# LedControl.net
KiCad netlist of a schematic drawn in Altium Designer
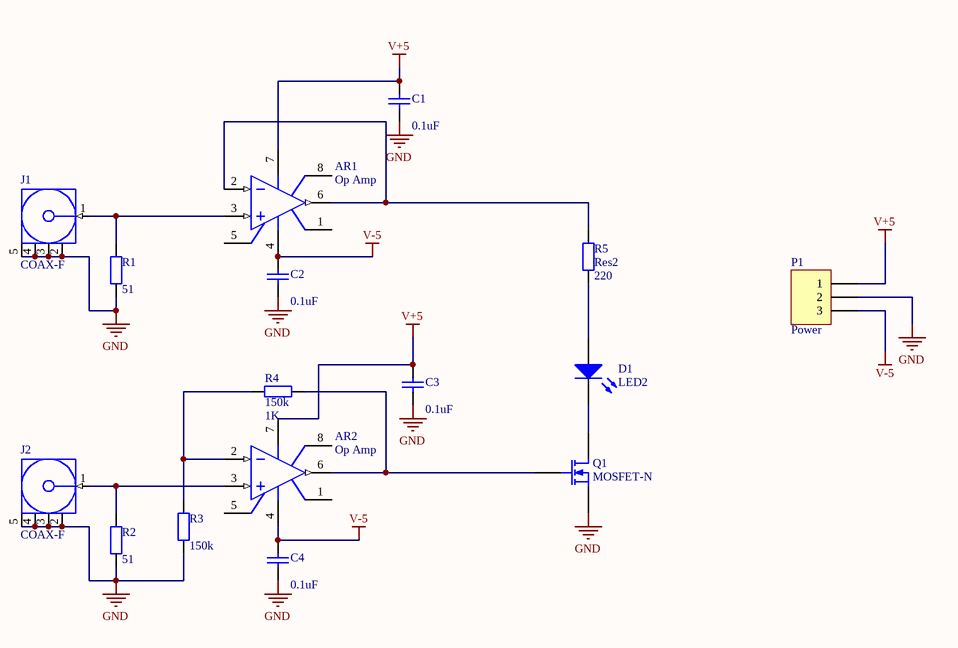
[diagram p0: LedControl.SchDoc]

(export (version "E")
  (design (tool "Eeschema 10.0.6"))
  (components
    (comp (ref "AR1")
      (value "Op Amp")
      (footprint "H-08A")
      (description "FET Operational Amplifier")
      (fields (field (name "PUBLISHER") "Altium Limited"))
      (libsource (lib "Miscellaneous Devices") (part "Op Amp"))
    )
    (comp (ref "AR2")
      (value "Op Amp")
      (footprint "H-08A")
      (description "FET Operational Amplifier")
      (fields (field (name "PUBLISHER") "Altium Limited"))
      (libsource (lib "Miscellaneous Devices") (part "Op Amp"))
    )
    (comp (ref "C1")
      (value "0.1uF")
      (footprint "RAD-0.3")
      (description "Capacitor")
      (fields (field (name "PUBLISHER") "Altium Limited"))
      (libsource (lib "Miscellaneous Devices") (part "Cap"))
    )
    (comp (ref "C2")
      (value "0.1uF")
      (footprint "RAD-0.3")
      (description "Capacitor")
      (fields (field (name "PUBLISHER") "Altium Limited"))
      (libsource (lib "Miscellaneous Devices") (part "Cap"))
    )
    (comp (ref "C3")
      (value "0.1uF")
      (footprint "RAD-0.3")
      (description "Capacitor")
      (fields (field (name "PUBLISHER") "Altium Limited"))
      (libsource (lib "Miscellaneous Devices") (part "Cap"))
    )
    (comp (ref "C4")
      (value "0.1uF")
      (footprint "RAD-0.3")
      (description "Capacitor")
      (fields (field (name "PUBLISHER") "Altium Limited"))
      (libsource (lib "Miscellaneous Devices") (part "Cap"))
    )
    (comp (ref "D1")
      (value "LED2")
      (footprint "3.2X1.6X1.1")
      (description "Typical RED, GREEN, YELLOW, AMBER GaAs LED")
      (fields (field (name "PUBLISHER") "Altium Limited"))
      (libsource (lib "Miscellaneous Devices") (part "LED2"))
    )
    (comp (ref "J1")
      (value "COAX-F")
      (footprint "MCX5.08-H5")
      (fields (field (name "PUBLISHER") "Altium Limited"))
      (libsource (lib "Miscellaneous Connectors") (part "COAX-F"))
    )
    (comp (ref "J2")
      (value "COAX-F")
      (footprint "MCX5.08-H5")
      (fields (field (name "PUBLISHER") "Altium Limited"))
      (libsource (lib "Miscellaneous Connectors") (part "COAX-F"))
    )
    (comp (ref "P1")
      (value "Power")
      (footprint "HDR1X3")
      (description "Header, 3-Pin")
      (fields (field (name "PUBLISHER") "Altium Limited"))
      (libsource (lib "Miscellaneous Connectors") (part "Header 3"))
    )
    (comp (ref "Q1")
      (value "MOSFET-N")
      (footprint "E3")
      (description "N-Channel MOSFET")
      (fields (field (name "PUBLISHER") "Altium Limited"))
      (libsource (lib "Miscellaneous Devices") (part "MOSFET-N"))
    )
    (comp (ref "R1")
      (value "51")
      (footprint "AXIAL-0.4")
      (description "Resistor")
      (fields (field (name "PUBLISHER") "Altium Limited"))
      (libsource (lib "Miscellaneous Devices") (part "Res2"))
    )
    (comp (ref "R2")
      (value "51")
      (footprint "AXIAL-0.4")
      (description "Resistor")
      (fields (field (name "PUBLISHER") "Altium Limited"))
      (libsource (lib "Miscellaneous Devices") (part "Res2"))
    )
    (comp (ref "R3")
      (value "150k")
      (footprint "AXIAL-0.4")
      (description "Resistor")
      (fields (field (name "PUBLISHER") "Altium Limited"))
      (libsource (lib "Miscellaneous Devices") (part "Res2"))
    )
    (comp (ref "R4")
      (value "150k")
      (footprint "AXIAL-0.4")
      (description "Resistor")
      (fields (field (name "ALTIUM_VALUE") "1K") (field (name "PUBLISHER") "Altium Limited"))
      (libsource (lib "") (part "Res2_1"))
    )
    (comp (ref "R5")
      (value "Res2")
      (footprint "AXIAL-0.4")
      (description "Resistor")
      (fields (field (name "ALTIUM_VALUE") "220") (field (name "PUBLISHER") "Altium Limited"))
      (libsource (lib "Miscellaneous Devices") (part "Res2"))
    )
  )
  (nets
    (net (code "1") (name "GND") (class "Default")
      (node (ref "C1") (pin "1") (pinfunction "1_1") (pintype "passive"))
      (node (ref "C2") (pin "1") (pinfunction "1_1") (pintype "passive"))
      (node (ref "C3") (pin "1") (pinfunction "1_1") (pintype "passive"))
      (node (ref "C4") (pin "1") (pinfunction "1_1") (pintype "passive"))
      (node (ref "J1") (pin "2") (pinfunction "GND_2") (pintype "power_in"))
      (node (ref "J1") (pin "3") (pinfunction "GND_3") (pintype "power_in"))
      (node (ref "J1") (pin "4") (pinfunction "GND_4") (pintype "power_in"))
      (node (ref "J1") (pin "5") (pinfunction "GND_5") (pintype "power_in"))
      (node (ref "J2") (pin "2") (pinfunction "GND_2") (pintype "power_in"))
      (node (ref "J2") (pin "3") (pinfunction "GND_3") (pintype "power_in"))
      (node (ref "J2") (pin "4") (pinfunction "GND_4") (pintype "power_in"))
      (node (ref "J2") (pin "5") (pinfunction "GND_5") (pintype "power_in"))
      (node (ref "P1") (pin "2") (pinfunction "2_2") (pintype "passive"))
      (node (ref "Q1") (pin "3") (pinfunction "S_3") (pintype "passive"))
      (node (ref "R1") (pin "1") (pinfunction "1_1") (pintype "passive"))
      (node (ref "R2") (pin "1") (pinfunction "1_1") (pintype "passive"))
      (node (ref "R3") (pin "1") (pinfunction "1_1") (pintype "passive"))
    )
    (net (code "2") (name "Net-(AR1-IN+)") (class "Default")
      (node (ref "AR1") (pin "3") (pinfunction "IN+_3") (pintype "input"))
      (node (ref "J1") (pin "1") (pinfunction "Signal_1") (pintype "input"))
      (node (ref "R1") (pin "2") (pinfunction "2_2") (pintype "passive"))
    )
    (net (code "3") (name "Net-(AR1-IN-)") (class "Default")
      (node (ref "AR1") (pin "2") (pinfunction "IN-_2") (pintype "input"))
      (node (ref "AR1") (pin "6") (pinfunction "OUT_6") (pintype "output"))
      (node (ref "R5") (pin "2") (pinfunction "2_2") (pintype "passive"))
    )
    (net (code "4") (name "Net-(AR2-IN+)") (class "Default")
      (node (ref "AR2") (pin "3") (pinfunction "IN+_3") (pintype "input"))
      (node (ref "J2") (pin "1") (pinfunction "Signal_1") (pintype "input"))
      (node (ref "R2") (pin "2") (pinfunction "2_2") (pintype "passive"))
    )
    (net (code "5") (name "Net-(AR2-IN-)") (class "Default")
      (node (ref "AR2") (pin "2") (pinfunction "IN-_2") (pintype "input"))
      (node (ref "R3") (pin "2") (pinfunction "2_2") (pintype "passive"))
      (node (ref "R4") (pin "1") (pinfunction "1_1") (pintype "passive"))
    )
    (net (code "6") (name "Net-(AR2-OUT)") (class "Default")
      (node (ref "AR2") (pin "6") (pinfunction "OUT_6") (pintype "output"))
      (node (ref "Q1") (pin "2") (pinfunction "G_2") (pintype "passive"))
      (node (ref "R4") (pin "2") (pinfunction "2_2") (pintype "passive"))
    )
    (net (code "7") (name "Net-(D1-A)") (class "Default")
      (node (ref "D1") (pin "1") (pinfunction "A_1") (pintype "passive"))
      (node (ref "R5") (pin "1") (pinfunction "1_1") (pintype "passive"))
    )
    (net (code "8") (name "Net-(D1-K)") (class "Default")
      (node (ref "D1") (pin "2") (pinfunction "K_2") (pintype "passive"))
      (node (ref "Q1") (pin "1") (pinfunction "D_1") (pintype "passive"))
    )
    (net (code "9") (name "V+5") (class "Default")
      (node (ref "AR1") (pin "7") (pinfunction "V+_7") (pintype "power_in"))
      (node (ref "AR2") (pin "7") (pinfunction "V+_7") (pintype "power_in"))
      (node (ref "C1") (pin "2") (pinfunction "2_2") (pintype "passive"))
      (node (ref "C3") (pin "2") (pinfunction "2_2") (pintype "passive"))
      (node (ref "P1") (pin "1") (pinfunction "1_1") (pintype "passive"))
    )
    (net (code "10") (name "V-5") (class "Default")
      (node (ref "AR1") (pin "4") (pinfunction "V-_4") (pintype "power_in"))
      (node (ref "AR2") (pin "4") (pinfunction "V-_4") (pintype "power_in"))
      (node (ref "C2") (pin "2") (pinfunction "2_2") (pintype "passive"))
      (node (ref "C4") (pin "2") (pinfunction "2_2") (pintype "passive"))
      (node (ref "P1") (pin "3") (pinfunction "3_3") (pintype "passive"))
    )
    (net (code "11") (name "unconnected-(AR1-OS_NUL-Pad1)") (class "Default")
      (node (ref "AR1") (pin "1") (pinfunction "OS_NUL_1") (pintype "passive"))
    )
    (net (code "12") (name "unconnected-(AR1-OS_NUL-Pad5)") (class "Default")
      (node (ref "AR1") (pin "5") (pinfunction "OS_NUL_5") (pintype "passive"))
    )
    (net (code "13") (name "unconnected-(AR1-TAB-Pad8)") (class "Default")
      (node (ref "AR1") (pin "8") (pinfunction "TAB_8") (pintype "passive"))
    )
    (net (code "14") (name "unconnected-(AR2-OS_NUL-Pad1)") (class "Default")
      (node (ref "AR2") (pin "1") (pinfunction "OS_NUL_1") (pintype "passive"))
    )
    (net (code "15") (name "unconnected-(AR2-OS_NUL-Pad5)") (class "Default")
      (node (ref "AR2") (pin "5") (pinfunction "OS_NUL_5") (pintype "passive"))
    )
    (net (code "16") (name "unconnected-(AR2-TAB-Pad8)") (class "Default")
      (node (ref "AR2") (pin "8") (pinfunction "TAB_8") (pintype "passive"))
    )
  )
)
